# Arduino_Micro_DRAM_Tester_3B.net
KiCad netlist of a schematic drawn in EAGLE
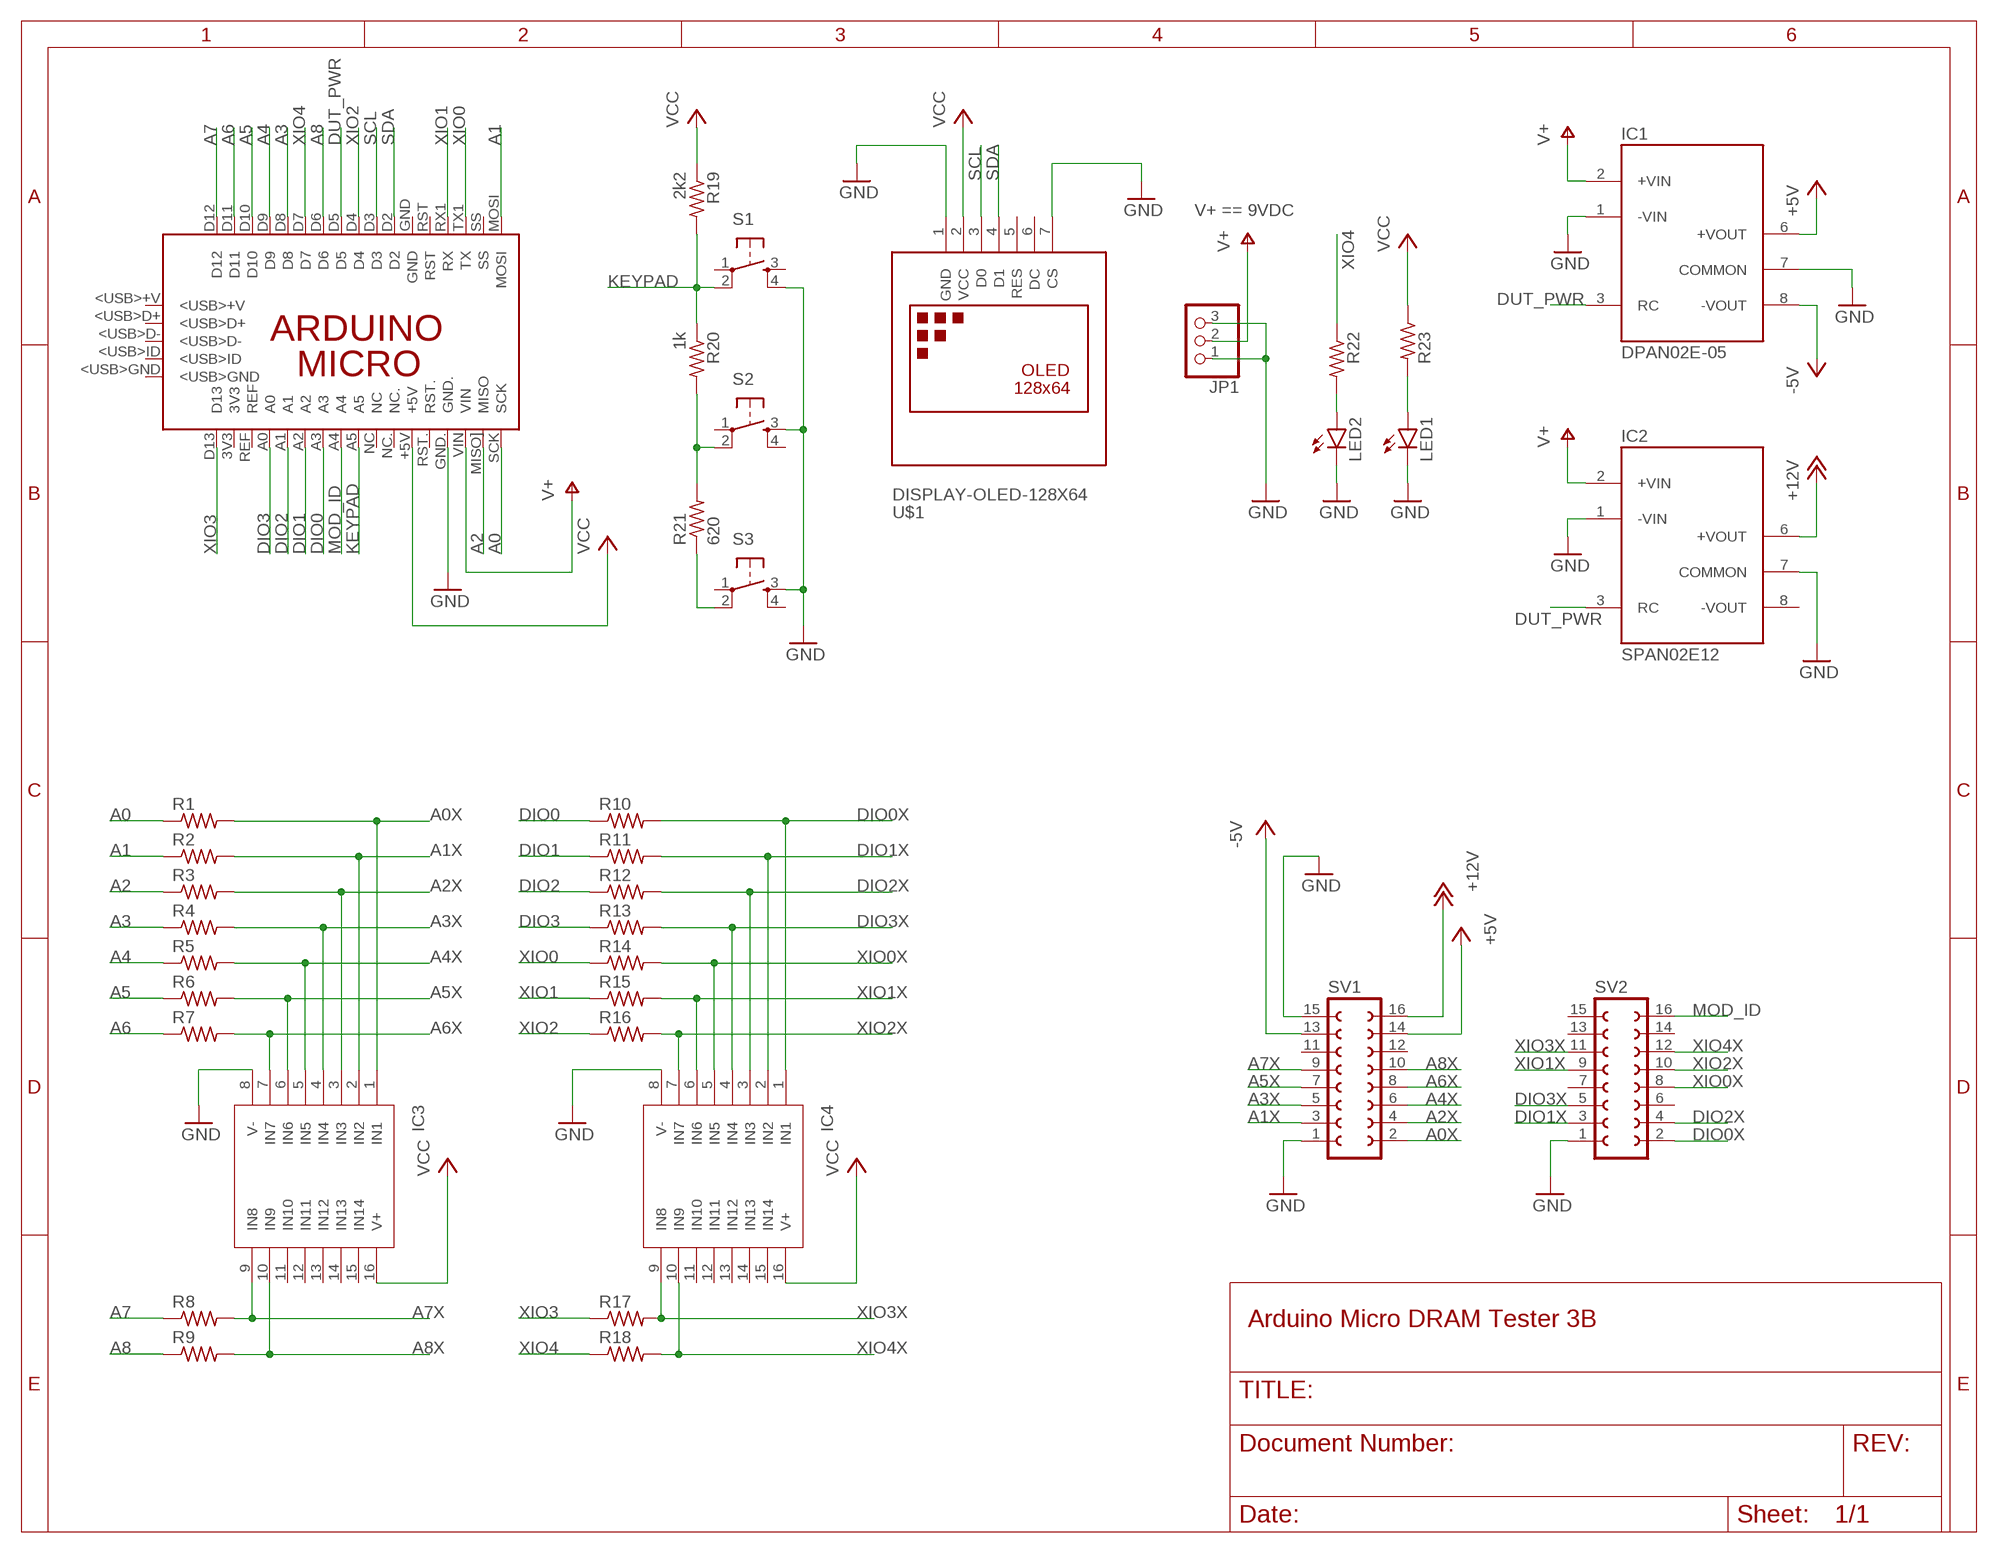
[diagram p0: schematic, sheet 1]

(export (version "E")
  (design (tool "Eeschema 10.0.6"))
  (components
    (comp (ref "IC1")
      (value "DPAN02E-05")
      (footprint "eagle-import:SIP7")
      (libsource (lib "eagle-import") (part "DPAN02"))
    )
    (comp (ref "IC2")
      (value "SPAN02E12")
      (footprint "eagle-import:SIP7")
      (libsource (lib "eagle-import") (part "DPAN02"))
    )
    (comp (ref "IC3")
      (value "SP720")
      (footprint "eagle-import:DIL16")
      (libsource (lib "eagle-import") (part "SP720"))
    )
    (comp (ref "IC4")
      (value "SP720")
      (footprint "eagle-import:DIL16")
      (libsource (lib "eagle-import") (part "SP720"))
    )
    (comp (ref "JP1")
      (value "PINHD-1X3/90")
      (footprint "eagle-import:1X03_90")
      (libsource (lib "eagle-import") (part "PINHD-1X3/90"))
    )
    (comp (ref "LED1")
      (value "LED5MM")
      (footprint "eagle-import:LED5MM")
      (libsource (lib "eagle-import") (part "LED5MM"))
    )
    (comp (ref "LED2")
      (value "LED5MM")
      (footprint "eagle-import:LED5MM")
      (libsource (lib "eagle-import") (part "LED5MM"))
    )
    (comp (ref "PCB1")
      (value "ARDUINO_MICRO")
      (footprint "eagle-import:ARDUINO_MICRO")
      (libsource (lib "eagle-import") (part "ARDUINO_MICRO"))
    )
    (comp (ref "R1")
      (value "R-US_0204/7")
      (footprint "eagle-import:0204_7")
      (libsource (lib "eagle-import") (part "R-US_0204/7"))
    )
    (comp (ref "R2")
      (value "R-US_0204/7")
      (footprint "eagle-import:0204_7")
      (libsource (lib "eagle-import") (part "R-US_0204/7"))
    )
    (comp (ref "R3")
      (value "R-US_0204/7")
      (footprint "eagle-import:0204_7")
      (libsource (lib "eagle-import") (part "R-US_0204/7"))
    )
    (comp (ref "R4")
      (value "R-US_0204/7")
      (footprint "eagle-import:0204_7")
      (libsource (lib "eagle-import") (part "R-US_0204/7"))
    )
    (comp (ref "R5")
      (value "R-US_0204/7")
      (footprint "eagle-import:0204_7")
      (libsource (lib "eagle-import") (part "R-US_0204/7"))
    )
    (comp (ref "R6")
      (value "R-US_0204/7")
      (footprint "eagle-import:0204_7")
      (libsource (lib "eagle-import") (part "R-US_0204/7"))
    )
    (comp (ref "R7")
      (value "R-US_0204/7")
      (footprint "eagle-import:0204_7")
      (libsource (lib "eagle-import") (part "R-US_0204/7"))
    )
    (comp (ref "R8")
      (value "R-US_0204/7")
      (footprint "eagle-import:0204_7")
      (libsource (lib "eagle-import") (part "R-US_0204/7"))
    )
    (comp (ref "R9")
      (value "R-US_0204/7")
      (footprint "eagle-import:0204_7")
      (libsource (lib "eagle-import") (part "R-US_0204/7"))
    )
    (comp (ref "R10")
      (value "R-US_0204/7")
      (footprint "eagle-import:0204_7")
      (libsource (lib "eagle-import") (part "R-US_0204/7"))
    )
    (comp (ref "R11")
      (value "R-US_0204/7")
      (footprint "eagle-import:0204_7")
      (libsource (lib "eagle-import") (part "R-US_0204/7"))
    )
    (comp (ref "R12")
      (value "R-US_0204/7")
      (footprint "eagle-import:0204_7")
      (libsource (lib "eagle-import") (part "R-US_0204/7"))
    )
    (comp (ref "R13")
      (value "R-US_0204/7")
      (footprint "eagle-import:0204_7")
      (libsource (lib "eagle-import") (part "R-US_0204/7"))
    )
    (comp (ref "R14")
      (value "R-US_0204/7")
      (footprint "eagle-import:0204_7")
      (libsource (lib "eagle-import") (part "R-US_0204/7"))
    )
    (comp (ref "R15")
      (value "R-US_0204/7")
      (footprint "eagle-import:0204_7")
      (libsource (lib "eagle-import") (part "R-US_0204/7"))
    )
    (comp (ref "R16")
      (value "R-US_0204/7")
      (footprint "eagle-import:0204_7")
      (libsource (lib "eagle-import") (part "R-US_0204/7"))
    )
    (comp (ref "R17")
      (value "R-US_0204/7")
      (footprint "eagle-import:0204_7")
      (libsource (lib "eagle-import") (part "R-US_0204/7"))
    )
    (comp (ref "R18")
      (value "R-US_0204/7")
      (footprint "eagle-import:0204_7")
      (libsource (lib "eagle-import") (part "R-US_0204/7"))
    )
    (comp (ref "R19")
      (value "2k2")
      (footprint "eagle-import:0204_7")
      (libsource (lib "eagle-import") (part "R-US_0204/7"))
    )
    (comp (ref "R20")
      (value "1k")
      (footprint "eagle-import:0204_7")
      (libsource (lib "eagle-import") (part "R-US_0204/7"))
    )
    (comp (ref "R21")
      (value "620")
      (footprint "eagle-import:0204_7")
      (libsource (lib "eagle-import") (part "R-US_0204/7"))
    )
    (comp (ref "R22")
      (value "R-US_0204/7")
      (footprint "eagle-import:0204_7")
      (libsource (lib "eagle-import") (part "R-US_0204/7"))
    )
    (comp (ref "R23")
      (value "R-US_0204/7")
      (footprint "eagle-import:0204_7")
      (libsource (lib "eagle-import") (part "R-US_0204/7"))
    )
    (comp (ref "S1")
      (value "TAC_SWITCHPTH")
      (footprint "eagle-import:TACTILE-PTH")
      (libsource (lib "eagle-import") (part "TAC_SWITCHPTH"))
    )
    (comp (ref "S2")
      (value "TAC_SWITCHPTH")
      (footprint "eagle-import:TACTILE-PTH")
      (libsource (lib "eagle-import") (part "TAC_SWITCHPTH"))
    )
    (comp (ref "S3")
      (value "TAC_SWITCHPTH")
      (footprint "eagle-import:TACTILE-PTH")
      (libsource (lib "eagle-import") (part "TAC_SWITCHPTH"))
    )
    (comp (ref "SV1")
      (value "FE08-2")
      (footprint "eagle-import:FE08-2")
      (libsource (lib "eagle-import") (part "FE08-2"))
    )
    (comp (ref "SV2")
      (value "FE08-2")
      (footprint "eagle-import:FE08-2")
      (libsource (lib "eagle-import") (part "FE08-2"))
    )
    (comp (ref "U$1")
      (value "DISPLAY-OLED-128X64")
      (footprint "eagle-import:DISPLAY-OLED-128X64")
      (libsource (lib "eagle-import") (part "DISPLAY-OLED-128X64"))
    )
  )
  (nets
    (net (code "1") (name "+5V") (class "Default")
      (node (ref "IC1") (pin "6") (pinfunction "+VOUT_6") (pintype "passive"))
      (node (ref "SV1") (pin "14") (pinfunction "14_14") (pintype "passive"))
    )
    (net (code "2") (name "+12V") (class "Default")
      (node (ref "IC2") (pin "6") (pinfunction "+VOUT_6") (pintype "passive"))
      (node (ref "SV1") (pin "16") (pinfunction "16_16") (pintype "passive"))
    )
    (net (code "3") (name "-5V") (class "Default")
      (node (ref "IC1") (pin "8") (pinfunction "-VOUT_8") (pintype "passive"))
      (node (ref "SV1") (pin "13") (pinfunction "13_13") (pintype "passive"))
    )
    (net (code "4") (name "/A0") (class "Default")
      (node (ref "PCB1") (pin "SCK") (pinfunction "SCK_SCK") (pintype "bidirectional"))
      (node (ref "R1") (pin "1") (pinfunction "1_1") (pintype "passive"))
    )
    (net (code "5") (name "/A0X") (class "Default")
      (node (ref "IC3") (pin "1") (pinfunction "IN1_1") (pintype "input"))
      (node (ref "R1") (pin "2") (pinfunction "2_2") (pintype "passive"))
      (node (ref "SV1") (pin "2") (pinfunction "2_2") (pintype "passive"))
    )
    (net (code "6") (name "/A1") (class "Default")
      (node (ref "PCB1") (pin "MOSI") (pinfunction "MOSI_MOSI") (pintype "bidirectional"))
      (node (ref "R2") (pin "1") (pinfunction "1_1") (pintype "passive"))
    )
    (net (code "7") (name "/A1X") (class "Default")
      (node (ref "IC3") (pin "2") (pinfunction "IN2_2") (pintype "input"))
      (node (ref "R2") (pin "2") (pinfunction "2_2") (pintype "passive"))
      (node (ref "SV1") (pin "3") (pinfunction "3_3") (pintype "passive"))
    )
    (net (code "8") (name "/A2") (class "Default")
      (node (ref "PCB1") (pin "MISO]") (pinfunction "MISO_MISO]") (pintype "bidirectional"))
      (node (ref "R3") (pin "1") (pinfunction "1_1") (pintype "passive"))
    )
    (net (code "9") (name "/A2X") (class "Default")
      (node (ref "IC3") (pin "3") (pinfunction "IN3_3") (pintype "input"))
      (node (ref "R3") (pin "2") (pinfunction "2_2") (pintype "passive"))
      (node (ref "SV1") (pin "4") (pinfunction "4_4") (pintype "passive"))
    )
    (net (code "10") (name "/A3") (class "Default")
      (node (ref "PCB1") (pin "D8") (pinfunction "D8_D8") (pintype "bidirectional"))
      (node (ref "R4") (pin "1") (pinfunction "1_1") (pintype "passive"))
    )
    (net (code "11") (name "/A3X") (class "Default")
      (node (ref "IC3") (pin "4") (pinfunction "IN4_4") (pintype "input"))
      (node (ref "R4") (pin "2") (pinfunction "2_2") (pintype "passive"))
      (node (ref "SV1") (pin "5") (pinfunction "5_5") (pintype "passive"))
    )
    (net (code "12") (name "/A4") (class "Default")
      (node (ref "PCB1") (pin "D9") (pinfunction "D9_D9") (pintype "bidirectional"))
      (node (ref "R5") (pin "1") (pinfunction "1_1") (pintype "passive"))
    )
    (net (code "13") (name "/A4X") (class "Default")
      (node (ref "IC3") (pin "5") (pinfunction "IN5_5") (pintype "input"))
      (node (ref "R5") (pin "2") (pinfunction "2_2") (pintype "passive"))
      (node (ref "SV1") (pin "6") (pinfunction "6_6") (pintype "passive"))
    )
    (net (code "14") (name "/A5") (class "Default")
      (node (ref "PCB1") (pin "D10") (pinfunction "D10_D10") (pintype "bidirectional"))
      (node (ref "R6") (pin "1") (pinfunction "1_1") (pintype "passive"))
    )
    (net (code "15") (name "/A5X") (class "Default")
      (node (ref "IC3") (pin "6") (pinfunction "IN6_6") (pintype "input"))
      (node (ref "R6") (pin "2") (pinfunction "2_2") (pintype "passive"))
      (node (ref "SV1") (pin "7") (pinfunction "7_7") (pintype "passive"))
    )
    (net (code "16") (name "/A6") (class "Default")
      (node (ref "PCB1") (pin "D11") (pinfunction "D11_D11") (pintype "bidirectional"))
      (node (ref "R7") (pin "1") (pinfunction "1_1") (pintype "passive"))
    )
    (net (code "17") (name "/A6X") (class "Default")
      (node (ref "IC3") (pin "7") (pinfunction "IN7_7") (pintype "input"))
      (node (ref "R7") (pin "2") (pinfunction "2_2") (pintype "passive"))
      (node (ref "SV1") (pin "8") (pinfunction "8_8") (pintype "passive"))
    )
    (net (code "18") (name "/A7") (class "Default")
      (node (ref "PCB1") (pin "D12") (pinfunction "D12_D12") (pintype "bidirectional"))
      (node (ref "R8") (pin "1") (pinfunction "1_1") (pintype "passive"))
    )
    (net (code "19") (name "/A7X") (class "Default")
      (node (ref "IC3") (pin "9") (pinfunction "IN8_9") (pintype "input"))
      (node (ref "R8") (pin "2") (pinfunction "2_2") (pintype "passive"))
      (node (ref "SV1") (pin "9") (pinfunction "9_9") (pintype "passive"))
    )
    (net (code "20") (name "/A8") (class "Default")
      (node (ref "PCB1") (pin "D6") (pinfunction "D6_D6") (pintype "bidirectional"))
      (node (ref "R9") (pin "1") (pinfunction "1_1") (pintype "passive"))
    )
    (net (code "21") (name "/A8X") (class "Default")
      (node (ref "IC3") (pin "10") (pinfunction "IN9_10") (pintype "input"))
      (node (ref "R9") (pin "2") (pinfunction "2_2") (pintype "passive"))
      (node (ref "SV1") (pin "10") (pinfunction "10_10") (pintype "passive"))
    )
    (net (code "22") (name "/DIO0") (class "Default")
      (node (ref "PCB1") (pin "A3") (pinfunction "A3_A3") (pintype "bidirectional"))
      (node (ref "R10") (pin "1") (pinfunction "1_1") (pintype "passive"))
    )
    (net (code "23") (name "/DIO0X") (class "Default")
      (node (ref "IC4") (pin "1") (pinfunction "IN1_1") (pintype "input"))
      (node (ref "R10") (pin "2") (pinfunction "2_2") (pintype "passive"))
      (node (ref "SV2") (pin "2") (pinfunction "2_2") (pintype "passive"))
    )
    (net (code "24") (name "/DIO1") (class "Default")
      (node (ref "PCB1") (pin "A2") (pinfunction "A2_A2") (pintype "bidirectional"))
      (node (ref "R11") (pin "1") (pinfunction "1_1") (pintype "passive"))
    )
    (net (code "25") (name "/DIO1X") (class "Default")
      (node (ref "IC4") (pin "2") (pinfunction "IN2_2") (pintype "input"))
      (node (ref "R11") (pin "2") (pinfunction "2_2") (pintype "passive"))
      (node (ref "SV2") (pin "3") (pinfunction "3_3") (pintype "passive"))
    )
    (net (code "26") (name "/DIO2") (class "Default")
      (node (ref "PCB1") (pin "A1") (pinfunction "A1_A1") (pintype "bidirectional"))
      (node (ref "R12") (pin "1") (pinfunction "1_1") (pintype "passive"))
    )
    (net (code "27") (name "/DIO2X") (class "Default")
      (node (ref "IC4") (pin "3") (pinfunction "IN3_3") (pintype "input"))
      (node (ref "R12") (pin "2") (pinfunction "2_2") (pintype "passive"))
      (node (ref "SV2") (pin "4") (pinfunction "4_4") (pintype "passive"))
    )
    (net (code "28") (name "/DIO3") (class "Default")
      (node (ref "PCB1") (pin "A0") (pinfunction "A0_A0") (pintype "bidirectional"))
      (node (ref "R13") (pin "1") (pinfunction "1_1") (pintype "passive"))
    )
    (net (code "29") (name "/DIO3X") (class "Default")
      (node (ref "IC4") (pin "4") (pinfunction "IN4_4") (pintype "input"))
      (node (ref "R13") (pin "2") (pinfunction "2_2") (pintype "passive"))
      (node (ref "SV2") (pin "5") (pinfunction "5_5") (pintype "passive"))
    )
    (net (code "30") (name "/DUT_PWR") (class "Default")
      (node (ref "IC1") (pin "3") (pinfunction "RC_3") (pintype "input"))
      (node (ref "IC2") (pin "3") (pinfunction "RC_3") (pintype "input"))
      (node (ref "PCB1") (pin "D5") (pinfunction "D5_D5") (pintype "bidirectional"))
    )
    (net (code "31") (name "/KEYPAD") (class "Default")
      (node (ref "PCB1") (pin "A5") (pinfunction "A5_A5") (pintype "bidirectional"))
      (node (ref "R19") (pin "2") (pinfunction "2_2") (pintype "passive"))
      (node (ref "R20") (pin "1") (pinfunction "1_1") (pintype "passive"))
      (node (ref "S1") (pin "2") (pinfunction "2_2") (pintype "passive"))
    )
    (net (code "32") (name "/MOD_ID") (class "Default")
      (node (ref "PCB1") (pin "A4") (pinfunction "A4_A4") (pintype "bidirectional"))
      (node (ref "SV2") (pin "16") (pinfunction "16_16") (pintype "passive"))
    )
    (net (code "33") (name "/SCL") (class "Default")
      (node (ref "PCB1") (pin "D3") (pinfunction "D3_D3") (pintype "bidirectional"))
      (node (ref "U$1") (pin "3") (pinfunction "D0_3") (pintype "bidirectional"))
    )
    (net (code "34") (name "/SDA") (class "Default")
      (node (ref "PCB1") (pin "D2") (pinfunction "D2_D2") (pintype "bidirectional"))
      (node (ref "U$1") (pin "4") (pinfunction "D1_4") (pintype "bidirectional"))
    )
    (net (code "35") (name "/XIO0") (class "Default")
      (node (ref "PCB1") (pin "TX1") (pinfunction "TX_TX1") (pintype "bidirectional"))
      (node (ref "R14") (pin "1") (pinfunction "1_1") (pintype "passive"))
    )
    (net (code "36") (name "/XIO0X") (class "Default")
      (node (ref "IC4") (pin "5") (pinfunction "IN5_5") (pintype "input"))
      (node (ref "R14") (pin "2") (pinfunction "2_2") (pintype "passive"))
      (node (ref "SV2") (pin "8") (pinfunction "8_8") (pintype "passive"))
    )
    (net (code "37") (name "/XIO1") (class "Default")
      (node (ref "PCB1") (pin "RX1") (pinfunction "RX_RX1") (pintype "bidirectional"))
      (node (ref "R15") (pin "1") (pinfunction "1_1") (pintype "passive"))
    )
    (net (code "38") (name "/XIO1X") (class "Default")
      (node (ref "IC4") (pin "6") (pinfunction "IN6_6") (pintype "input"))
      (node (ref "R15") (pin "2") (pinfunction "2_2") (pintype "passive"))
      (node (ref "SV2") (pin "9") (pinfunction "9_9") (pintype "passive"))
    )
    (net (code "39") (name "/XIO2") (class "Default")
      (node (ref "PCB1") (pin "D4") (pinfunction "D4_D4") (pintype "bidirectional"))
      (node (ref "R16") (pin "1") (pinfunction "1_1") (pintype "passive"))
    )
    (net (code "40") (name "/XIO2X") (class "Default")
      (node (ref "IC4") (pin "7") (pinfunction "IN7_7") (pintype "input"))
      (node (ref "R16") (pin "2") (pinfunction "2_2") (pintype "passive"))
      (node (ref "SV2") (pin "10") (pinfunction "10_10") (pintype "passive"))
    )
    (net (code "41") (name "/XIO3") (class "Default")
      (node (ref "PCB1") (pin "D13") (pinfunction "D13_D13") (pintype "bidirectional"))
      (node (ref "R17") (pin "1") (pinfunction "1_1") (pintype "passive"))
    )
    (net (code "42") (name "/XIO3X") (class "Default")
      (node (ref "IC4") (pin "9") (pinfunction "IN8_9") (pintype "input"))
      (node (ref "R17") (pin "2") (pinfunction "2_2") (pintype "passive"))
      (node (ref "SV2") (pin "11") (pinfunction "11_11") (pintype "passive"))
    )
    (net (code "43") (name "/XIO4") (class "Default")
      (node (ref "PCB1") (pin "D7") (pinfunction "D7_D7") (pintype "bidirectional"))
      (node (ref "R18") (pin "1") (pinfunction "1_1") (pintype "passive"))
      (node (ref "R22") (pin "1") (pinfunction "1_1") (pintype "passive"))
    )
    (net (code "44") (name "/XIO4X") (class "Default")
      (node (ref "IC4") (pin "10") (pinfunction "IN9_10") (pintype "input"))
      (node (ref "R18") (pin "2") (pinfunction "2_2") (pintype "passive"))
      (node (ref "SV2") (pin "12") (pinfunction "12_12") (pintype "passive"))
    )
    (net (code "45") (name "GND") (class "Default")
      (node (ref "IC1") (pin "1") (pinfunction "-VIN_1") (pintype "input"))
      (node (ref "IC1") (pin "7") (pinfunction "COMMON_7") (pintype "passive"))
      (node (ref "IC2") (pin "1") (pinfunction "-VIN_1") (pintype "input"))
      (node (ref "IC2") (pin "7") (pinfunction "COMMON_7") (pintype "passive"))
      (node (ref "IC3") (pin "8") (pinfunction "V-_8") (pintype "input"))
      (node (ref "IC4") (pin "8") (pinfunction "V-_8") (pintype "input"))
      (node (ref "JP1") (pin "1") (pinfunction "1_1") (pintype "passive"))
      (node (ref "JP1") (pin "3") (pinfunction "3_3") (pintype "passive"))
      (node (ref "LED1") (pin "K") (pinfunction "C_K") (pintype "passive"))
      (node (ref "LED2") (pin "K") (pinfunction "C_K") (pintype "passive"))
      (node (ref "PCB1") (pin "GND.") (pinfunction "GND._GND.") (pintype "bidirectional"))
      (node (ref "S1") (pin "4") (pinfunction "4_4") (pintype "passive"))
      (node (ref "S2") (pin "3") (pinfunction "3_3") (pintype "passive"))
      (node (ref "S3") (pin "3") (pinfunction "3_3") (pintype "passive"))
      (node (ref "SV1") (pin "1") (pinfunction "1_1") (pintype "passive"))
      (node (ref "SV1") (pin "15") (pinfunction "15_15") (pintype "passive"))
      (node (ref "SV2") (pin "1") (pinfunction "1_1") (pintype "passive"))
      (node (ref "U$1") (pin "1") (pinfunction "GND_1") (pintype "power_in"))
      (node (ref "U$1") (pin "7") (pinfunction "CS_7") (pintype "bidirectional"))
    )
    (net (code "46") (name "Net-(LED1-PadA)") (class "Default")
      (node (ref "LED1") (pin "A") (pinfunction "A_A") (pintype "passive"))
      (node (ref "R23") (pin "2") (pinfunction "2_2") (pintype "passive"))
    )
    (net (code "47") (name "Net-(LED2-PadA)") (class "Default")
      (node (ref "LED2") (pin "A") (pinfunction "A_A") (pintype "passive"))
      (node (ref "R22") (pin "2") (pinfunction "2_2") (pintype "passive"))
    )
    (net (code "48") (name "Net-(R20-Pad2)") (class "Default")
      (node (ref "R20") (pin "2") (pinfunction "2_2") (pintype "passive"))
      (node (ref "R21") (pin "2") (pinfunction "2_2") (pintype "passive"))
      (node (ref "S2") (pin "2") (pinfunction "2_2") (pintype "passive"))
    )
    (net (code "49") (name "Net-(R21-Pad1)") (class "Default")
      (node (ref "R21") (pin "1") (pinfunction "1_1") (pintype "passive"))
      (node (ref "S3") (pin "2") (pinfunction "2_2") (pintype "passive"))
    )
    (net (code "50") (name "V+") (class "Default")
      (node (ref "IC1") (pin "2") (pinfunction "+VIN_2") (pintype "input"))
      (node (ref "IC2") (pin "2") (pinfunction "+VIN_2") (pintype "input"))
      (node (ref "JP1") (pin "2") (pinfunction "2_2") (pintype "passive"))
      (node (ref "PCB1") (pin "VIN") (pinfunction "VIN_VIN") (pintype "bidirectional"))
    )
    (net (code "51") (name "VCC") (class "Default")
      (node (ref "IC3") (pin "16") (pinfunction "V+_16") (pintype "input"))
      (node (ref "IC4") (pin "16") (pinfunction "V+_16") (pintype "input"))
      (node (ref "PCB1") (pin "+5V") (pinfunction "+5V_+5V") (pintype "bidirectional"))
      (node (ref "R19") (pin "1") (pinfunction "1_1") (pintype "passive"))
      (node (ref "R23") (pin "1") (pinfunction "1_1") (pintype "passive"))
      (node (ref "U$1") (pin "2") (pinfunction "VCC_2") (pintype "power_in"))
    )
    (net (code "52") (name "unconnected-(IC2--VOUT-Pad8)") (class "Default")
      (node (ref "IC2") (pin "8") (pinfunction "-VOUT_8") (pintype "passive"))
    )
    (net (code "53") (name "unconnected-(IC3-IN10-Pad11)") (class "Default")
      (node (ref "IC3") (pin "11") (pinfunction "IN10_11") (pintype "input"))
    )
    (net (code "54") (name "unconnected-(IC3-IN11-Pad12)") (class "Default")
      (node (ref "IC3") (pin "12") (pinfunction "IN11_12") (pintype "input"))
    )
    (net (code "55") (name "unconnected-(IC3-IN12-Pad13)") (class "Default")
      (node (ref "IC3") (pin "13") (pinfunction "IN12_13") (pintype "input"))
    )
    (net (code "56") (name "unconnected-(IC3-IN13-Pad14)") (class "Default")
      (node (ref "IC3") (pin "14") (pinfunction "IN13_14") (pintype "input"))
    )
    (net (code "57") (name "unconnected-(IC3-IN14-Pad15)") (class "Default")
      (node (ref "IC3") (pin "15") (pinfunction "IN14_15") (pintype "input"))
    )
    (net (code "58") (name "unconnected-(IC4-IN10-Pad11)") (class "Default")
      (node (ref "IC4") (pin "11") (pinfunction "IN10_11") (pintype "input"))
    )
    (net (code "59") (name "unconnected-(IC4-IN11-Pad12)") (class "Default")
      (node (ref "IC4") (pin "12") (pinfunction "IN11_12") (pintype "input"))
    )
    (net (code "60") (name "unconnected-(IC4-IN12-Pad13)") (class "Default")
      (node (ref "IC4") (pin "13") (pinfunction "IN12_13") (pintype "input"))
    )
    (net (code "61") (name "unconnected-(IC4-IN13-Pad14)") (class "Default")
      (node (ref "IC4") (pin "14") (pinfunction "IN13_14") (pintype "input"))
    )
    (net (code "62") (name "unconnected-(IC4-IN14-Pad15)") (class "Default")
      (node (ref "IC4") (pin "15") (pinfunction "IN14_15") (pintype "input"))
    )
    (net (code "63") (name "unconnected-(PCB1-Pad3V3)") (class "Default")
      (node (ref "PCB1") (pin "3V3") (pinfunction "3V3_3V3") (pintype "bidirectional"))
    )
    (net (code "64") (name "unconnected-(PCB1-Pad<USB>+V)") (class "Default")
      (node (ref "PCB1") (pin "<USB>+V") (pinfunction "<USB>+V_<USB>+V") (pintype "bidirectional"))
    )
    (net (code "65") (name "unconnected-(PCB1-Pad<USB>D+)") (class "Default")
      (node (ref "PCB1") (pin "<USB>D+") (pinfunction "<USB>D+_<USB>D+") (pintype "bidirectional"))
    )
    (net (code "66") (name "unconnected-(PCB1-Pad<USB>D-)") (class "Default")
      (node (ref "PCB1") (pin "<USB>D-") (pinfunction "<USB>D-_<USB>D-") (pintype "bidirectional"))
    )
    (net (code "67") (name "unconnected-(PCB1-Pad<USB>GND)") (class "Default")
      (node (ref "PCB1") (pin "<USB>GND") (pinfunction "<USB>GND_<USB>GND") (pintype "bidirectional"))
    )
    (net (code "68") (name "unconnected-(PCB1-Pad<USB>ID)") (class "Default")
      (node (ref "PCB1") (pin "<USB>ID") (pinfunction "<USB>ID_<USB>ID") (pintype "bidirectional"))
    )
    (net (code "69") (name "unconnected-(PCB1-PadGND)") (class "Default")
      (node (ref "PCB1") (pin "GND") (pinfunction "GND_GND") (pintype "bidirectional"))
    )
    (net (code "70") (name "unconnected-(PCB1-PadNC)") (class "Default")
      (node (ref "PCB1") (pin "NC") (pinfunction "NC_NC") (pintype "bidirectional"))
    )
    (net (code "71") (name "unconnected-(PCB1-PadNC.)") (class "Default")
      (node (ref "PCB1") (pin "NC.") (pinfunction "NC._NC.") (pintype "bidirectional"))
    )
    (net (code "72") (name "unconnected-(PCB1-PadREF)") (class "Default")
      (node (ref "PCB1") (pin "REF") (pinfunction "REF_REF") (pintype "bidirectional"))
    )
    (net (code "73") (name "unconnected-(PCB1-PadRST)") (class "Default")
      (node (ref "PCB1") (pin "RST") (pinfunction "RST_RST") (pintype "bidirectional"))
    )
    (net (code "74") (name "unconnected-(PCB1-PadRST.)") (class "Default")
      (node (ref "PCB1") (pin "RST.") (pinfunction "RST._RST.") (pintype "bidirectional"))
    )
    (net (code "75") (name "unconnected-(PCB1-PadSS)") (class "Default")
      (node (ref "PCB1") (pin "SS") (pinfunction "SS_SS") (pintype "bidirectional"))
    )
    (net (code "76") (name "unconnected-(S1-Pad1)") (class "Default")
      (node (ref "S1") (pin "1") (pinfunction "1_1") (pintype "passive"))
    )
    (net (code "77") (name "unconnected-(S1-Pad3)") (class "Default")
      (node (ref "S1") (pin "3") (pinfunction "3_3") (pintype "passive"))
    )
    (net (code "78") (name "unconnected-(S2-Pad1)") (class "Default")
      (node (ref "S2") (pin "1") (pinfunction "1_1") (pintype "passive"))
    )
    (net (code "79") (name "unconnected-(S2-Pad4)") (class "Default")
      (node (ref "S2") (pin "4") (pinfunction "4_4") (pintype "passive"))
    )
    (net (code "80") (name "unconnected-(S3-Pad1)") (class "Default")
      (node (ref "S3") (pin "1") (pinfunction "1_1") (pintype "passive"))
    )
    (net (code "81") (name "unconnected-(S3-Pad4)") (class "Default")
      (node (ref "S3") (pin "4") (pinfunction "4_4") (pintype "passive"))
    )
    (net (code "82") (name "unconnected-(SV1-Pad11)") (class "Default")
      (node (ref "SV1") (pin "11") (pinfunction "11_11") (pintype "passive"))
    )
    (net (code "83") (name "unconnected-(SV1-Pad12)") (class "Default")
      (node (ref "SV1") (pin "12") (pinfunction "12_12") (pintype "passive"))
    )
    (net (code "84") (name "unconnected-(SV2-Pad6)") (class "Default")
      (node (ref "SV2") (pin "6") (pinfunction "6_6") (pintype "passive"))
    )
    (net (code "85") (name "unconnected-(SV2-Pad7)") (class "Default")
      (node (ref "SV2") (pin "7") (pinfunction "7_7") (pintype "passive"))
    )
    (net (code "86") (name "unconnected-(SV2-Pad13)") (class "Default")
      (node (ref "SV2") (pin "13") (pinfunction "13_13") (pintype "passive"))
    )
    (net (code "87") (name "unconnected-(SV2-Pad14)") (class "Default")
      (node (ref "SV2") (pin "14") (pinfunction "14_14") (pintype "passive"))
    )
    (net (code "88") (name "unconnected-(SV2-Pad15)") (class "Default")
      (node (ref "SV2") (pin "15") (pinfunction "15_15") (pintype "passive"))
    )
    (net (code "89") (name "unconnected-(U$1-DC-Pad6)") (class "Default")
      (node (ref "U$1") (pin "6") (pinfunction "DC_6") (pintype "bidirectional"))
    )
    (net (code "90") (name "unconnected-(U$1-RES-Pad5)") (class "Default")
      (node (ref "U$1") (pin "5") (pinfunction "RES_5") (pintype "bidirectional"))
    )
  )
)
